# Sheet3.net
KiCad netlist of a schematic drawn in Altium Designer
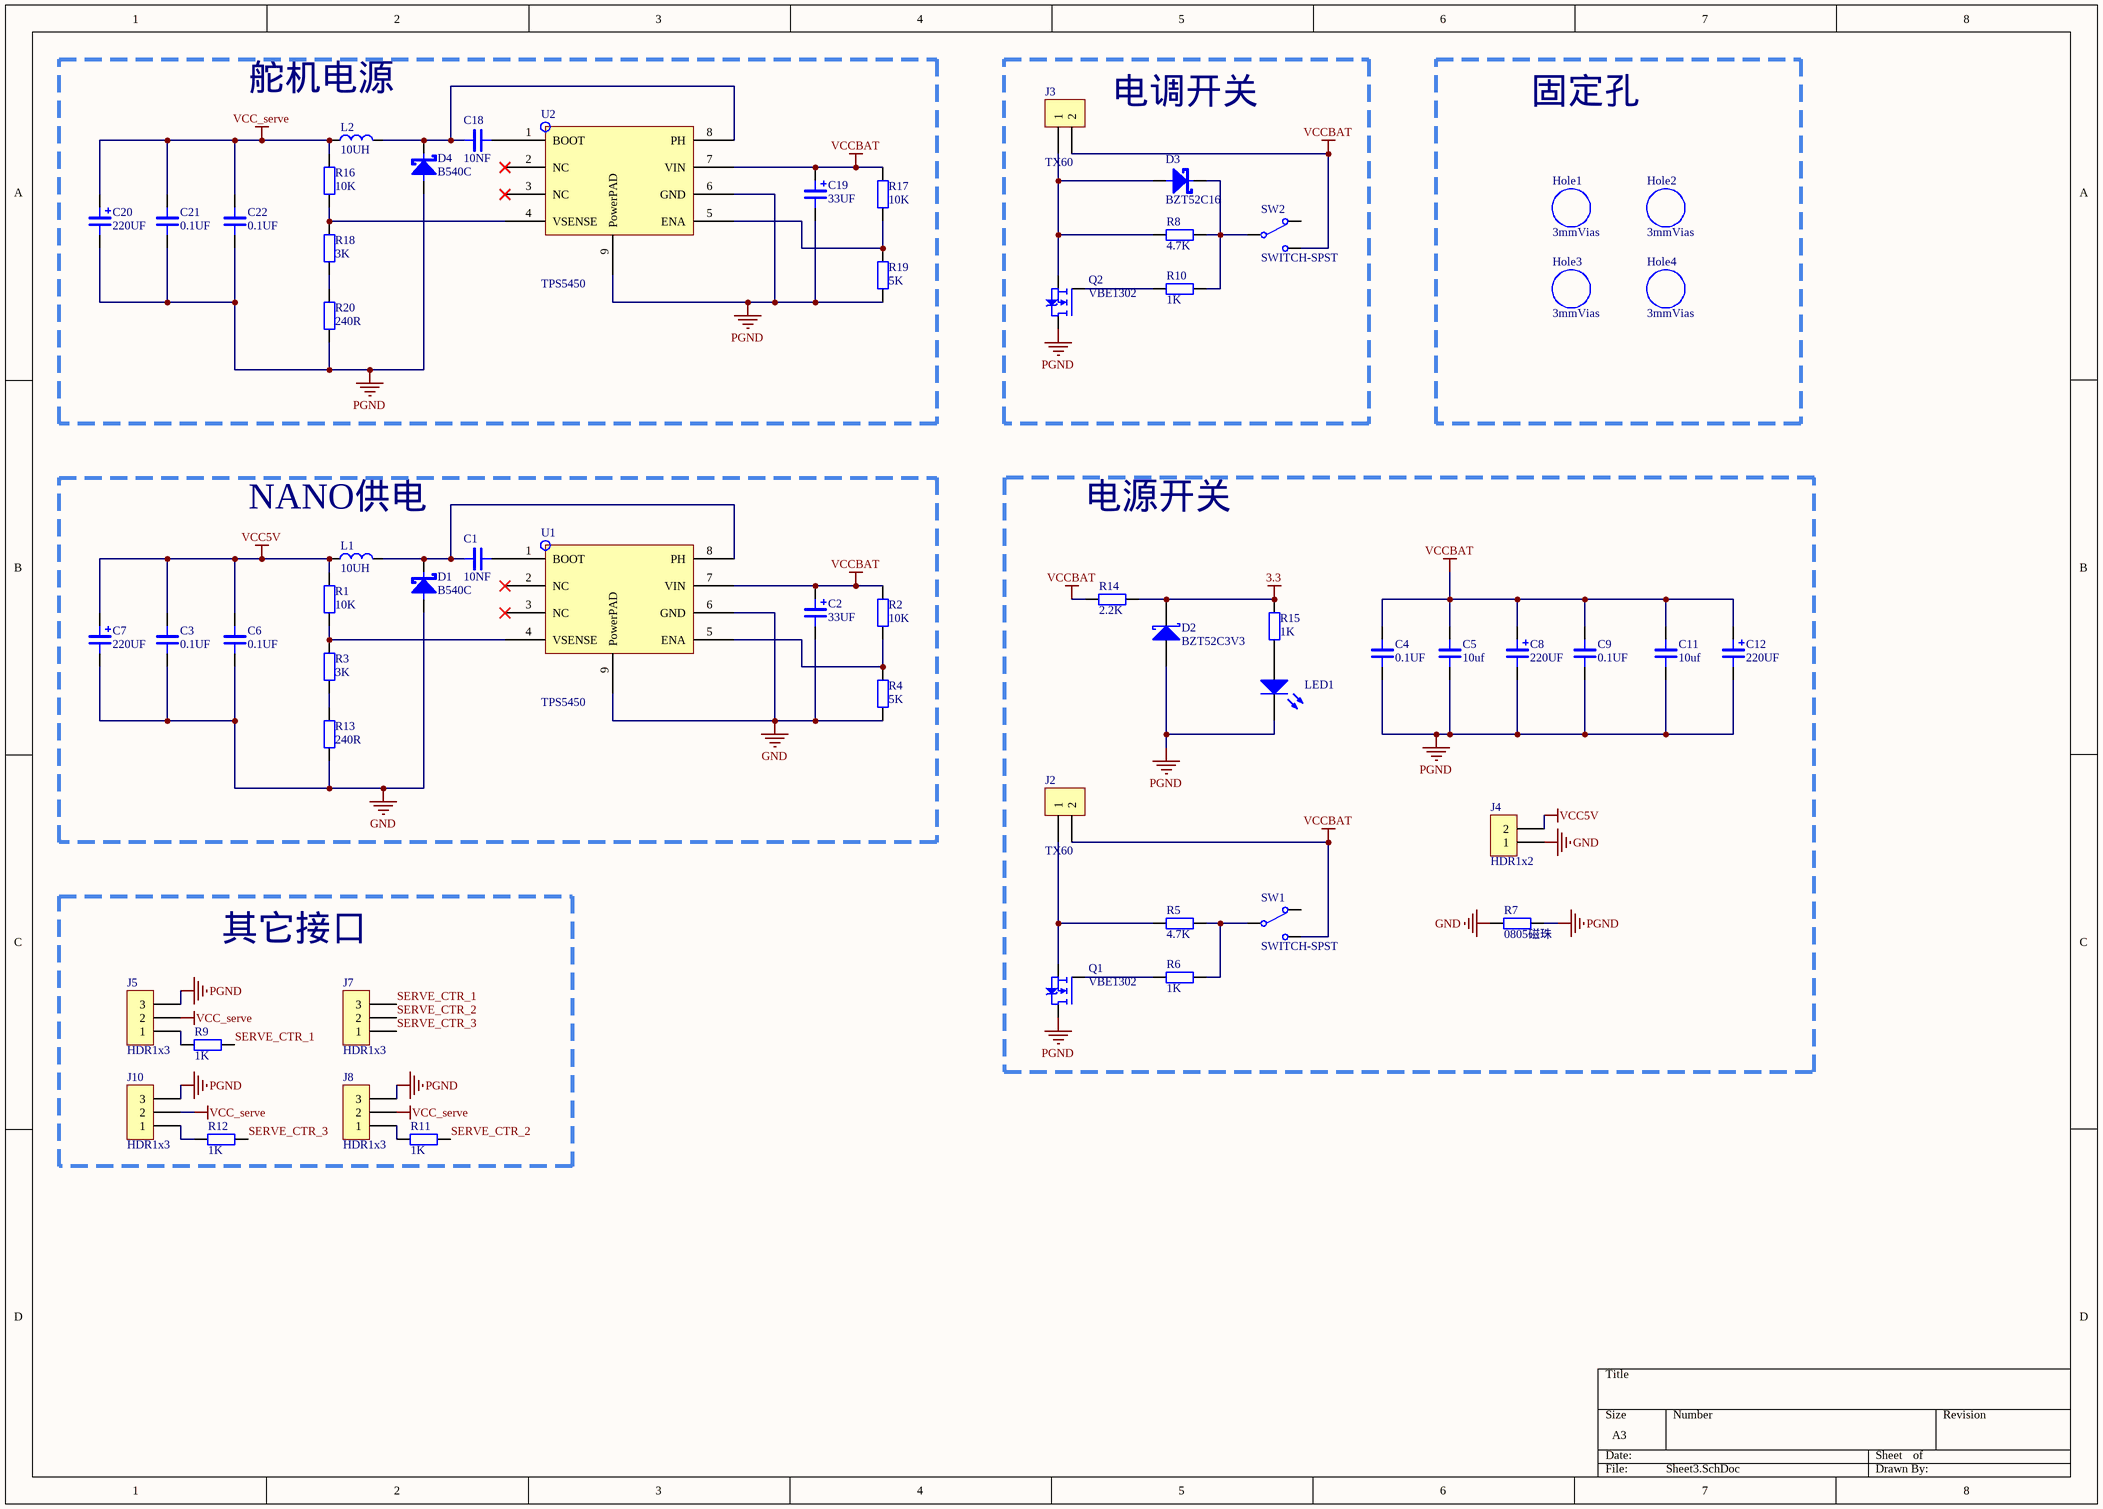
[diagram p0: Sheet3.SchDoc]

(export (version "E")
  (design (tool "Eeschema 10.0.6"))
  (components
    (comp (ref "C1")
      (value "10NF")
      (footprint "0603")
      (description "Capacitor")
      (libsource (lib "General") (part "CAP"))
    )
    (comp (ref "C2")
      (value "33UF")
      (footprint "DIP-EC2.5X5X11")
      (description "Tantalum Capacitor")
      (libsource (lib "General") (part "CAP-TANTALUM"))
    )
    (comp (ref "C3")
      (value "0.1UF")
      (footprint "0603")
      (description "Capacitor")
      (libsource (lib "General") (part "CAP"))
    )
    (comp (ref "C4")
      (value "0.1UF")
      (footprint "0603")
      (description "Capacitor")
      (libsource (lib "General") (part "CAP"))
    )
    (comp (ref "C5")
      (value "10uf")
      (footprint "0603")
      (description "Capacitor")
      (libsource (lib "General") (part "CAP"))
    )
    (comp (ref "C6")
      (value "0.1UF")
      (footprint "0603")
      (description "Capacitor")
      (libsource (lib "General") (part "CAP"))
    )
    (comp (ref "C7")
      (value "220UF")
      (footprint "DIP-EC3.5X8X11.5")
      (description "Tantalum Capacitor")
      (libsource (lib "General") (part "CAP-TANTALUM"))
    )
    (comp (ref "C8")
      (value "220UF")
      (footprint "DIP-EC3.5X8X11.5")
      (description "Tantalum Capacitor")
      (libsource (lib "General") (part "CAP-TANTALUM"))
    )
    (comp (ref "C9")
      (value "0.1UF")
      (footprint "0603")
      (description "Capacitor")
      (libsource (lib "General") (part "CAP"))
    )
    (comp (ref "C11")
      (value "10uf")
      (footprint "0603")
      (description "Capacitor")
      (libsource (lib "General") (part "CAP"))
    )
    (comp (ref "C12")
      (value "220UF")
      (footprint "DIP-EC3.5X8X11.5")
      (description "Tantalum Capacitor")
      (libsource (lib "General") (part "CAP-TANTALUM"))
    )
    (comp (ref "C18")
      (value "10NF")
      (footprint "0603")
      (description "Capacitor")
      (libsource (lib "General") (part "CAP"))
    )
    (comp (ref "C19")
      (value "33UF")
      (footprint "DIP-EC2.5X5X11")
      (description "Tantalum Capacitor")
      (libsource (lib "General") (part "CAP-TANTALUM"))
    )
    (comp (ref "C20")
      (value "220UF")
      (footprint "DIP-EC3.5X8X11.5")
      (description "Tantalum Capacitor")
      (libsource (lib "General") (part "CAP-TANTALUM"))
    )
    (comp (ref "C21")
      (value "0.1UF")
      (footprint "0603")
      (description "Capacitor")
      (libsource (lib "General") (part "CAP"))
    )
    (comp (ref "C22")
      (value "0.1UF")
      (footprint "0603")
      (description "Capacitor")
      (libsource (lib "General") (part "CAP"))
    )
    (comp (ref "D1")
      (value "B540C")
      (footprint "B540C")
      (description "Schottky Diode")
      (libsource (lib "General") (part "SS5x"))
    )
    (comp (ref "D2")
      (value "BZT52C3V3")
      (footprint "sod123")
      (description "Schottky Rectifier")
      (fields (field (name "PUBLISHER") "Altium Limited"))
      (libsource (lib "Miscellaneous Devices") (part "Diode 18TQ045"))
    )
    (comp (ref "D3")
      (value "BZT52C16")
      (footprint "sod123")
      (description "Schottky Diode")
      (libsource (lib "General") (part "SS5x"))
    )
    (comp (ref "D4")
      (value "B540C")
      (footprint "B540C")
      (description "Schottky Diode")
      (libsource (lib "General") (part "SS5x"))
    )
    (comp (ref "Hole1") (value "3mmVias") (footprint "3mm") (libsource (lib "General") (part "3mmVias")))
    (comp (ref "Hole2") (value "3mmVias") (footprint "3mm") (libsource (lib "General") (part "3mmVias")))
    (comp (ref "Hole3") (value "3mmVias") (footprint "3mm") (libsource (lib "General") (part "3mmVias")))
    (comp (ref "Hole4") (value "3mmVias") (footprint "3mm") (libsource (lib "General") (part "3mmVias")))
    (comp (ref "J2")
      (value "TX60")
      (footprint "焊盘")
      (description "Connector")
      (libsource (lib "General") (part "HDR1x2"))
    )
    (comp (ref "J3")
      (value "TX60")
      (footprint "焊盘")
      (description "Connector")
      (libsource (lib "General") (part "HDR1x2"))
    )
    (comp (ref "J4")
      (value "HDR1x2")
      (footprint "KF301")
      (description "Connector")
      (libsource (lib "") (part "HDR1x2_1"))
    )
    (comp (ref "J5")
      (value "HDR1x3")
      (footprint "PIN-3-2.54-1.0")
      (description "Connector")
      (libsource (lib "General") (part "HDR1x3"))
    )
    (comp (ref "J7")
      (value "HDR1x3")
      (footprint "PIN-3-2.54-1.0")
      (description "Connector")
      (libsource (lib "General") (part "HDR1x3"))
    )
    (comp (ref "J8")
      (value "HDR1x3")
      (footprint "PIN-3-2.54-1.0")
      (description "Connector")
      (libsource (lib "General") (part "HDR1x3"))
    )
    (comp (ref "J10")
      (value "HDR1x3")
      (footprint "PIN-3-2.54-1.0")
      (description "Connector")
      (libsource (lib "General") (part "HDR1x3"))
    )
    (comp (ref "L1")
      (value "10UH")
      (footprint "CDRH74")
      (description "Inductance")
      (libsource (lib "General") (part "INDUCTANCE"))
    )
    (comp (ref "L2")
      (value "10UH")
      (footprint "CDRH74")
      (description "Inductance")
      (libsource (lib "General") (part "INDUCTANCE"))
    )
    (comp (ref "LED1")
      (value "LED0")
      (footprint "0603-led")
      (description "Typical INFRARED GaAs LED")
      (fields (field (name "PUBLISHER") "Altium Limited"))
      (libsource (lib "Miscellaneous Devices") (part "LED0"))
    )
    (comp (ref "Q1")
      (value "VBE1302")
      (footprint "TO-252-2")
      (description "N-Channel MOSFET")
      (libsource (lib "General") (part "FDB52N20"))
    )
    (comp (ref "Q2")
      (value "VBE1302")
      (footprint "TO-252-2")
      (description "N-Channel MOSFET")
      (libsource (lib "General") (part "FDB52N20"))
    )
    (comp (ref "R1")
      (value "10K")
      (footprint "0603")
      (description "Resistor")
      (libsource (lib "General") (part "RES"))
    )
    (comp (ref "R2")
      (value "10K")
      (footprint "0603")
      (description "Resistor")
      (libsource (lib "General") (part "RES"))
    )
    (comp (ref "R3")
      (value "3K")
      (footprint "0603")
      (description "Resistor")
      (libsource (lib "General") (part "RES"))
    )
    (comp (ref "R4")
      (value "5K")
      (footprint "0603")
      (description "Resistor")
      (libsource (lib "General") (part "RES"))
    )
    (comp (ref "R5")
      (value "4.7K")
      (footprint "0603")
      (description "Resistor")
      (libsource (lib "") (part "RES_1"))
    )
    (comp (ref "R6")
      (value "1K")
      (footprint "0603")
      (description "Resistor")
      (libsource (lib "") (part "RES_1"))
    )
    (comp (ref "R7")
      (value "0805磁珠")
      (footprint "0805")
      (description "Resistor")
      (libsource (lib "") (part "RES_2"))
    )
    (comp (ref "R8")
      (value "4.7K")
      (footprint "0603")
      (description "Resistor")
      (libsource (lib "") (part "RES_1"))
    )
    (comp (ref "R9")
      (value "1K")
      (footprint "0603")
      (description "Resistor")
      (libsource (lib "") (part "RES_1"))
    )
    (comp (ref "R10")
      (value "1K")
      (footprint "0603")
      (description "Resistor")
      (libsource (lib "") (part "RES_1"))
    )
    (comp (ref "R11")
      (value "1K")
      (footprint "0603")
      (description "Resistor")
      (libsource (lib "") (part "RES_1"))
    )
    (comp (ref "R12")
      (value "1K")
      (footprint "0603")
      (description "Resistor")
      (libsource (lib "") (part "RES_1"))
    )
    (comp (ref "R13")
      (value "240R")
      (footprint "0603")
      (description "Resistor")
      (libsource (lib "General") (part "RES"))
    )
    (comp (ref "R14")
      (value "2.2K")
      (footprint "0603")
      (description "Resistor")
      (libsource (lib "") (part "RES_2"))
    )
    (comp (ref "R15")
      (value "1K")
      (footprint "0603")
      (description "Resistor")
      (libsource (lib "") (part "RES_3"))
    )
    (comp (ref "R16")
      (value "10K")
      (footprint "0603")
      (description "Resistor")
      (libsource (lib "General") (part "RES"))
    )
    (comp (ref "R17")
      (value "10K")
      (footprint "0603")
      (description "Resistor")
      (libsource (lib "General") (part "RES"))
    )
    (comp (ref "R18")
      (value "3K")
      (footprint "0603")
      (description "Resistor")
      (libsource (lib "General") (part "RES"))
    )
    (comp (ref "R19")
      (value "5K")
      (footprint "0603")
      (description "Resistor")
      (libsource (lib "General") (part "RES"))
    )
    (comp (ref "R20")
      (value "240R")
      (footprint "0603")
      (description "Resistor")
      (libsource (lib "General") (part "RES"))
    )
    (comp (ref "SW1")
      (value "SWITCH-SPST")
      (footprint "ss12d10")
      (description "Switch")
      (libsource (lib "General") (part "SWITCH-SPST"))
    )
    (comp (ref "SW2")
      (value "SWITCH-SPST")
      (footprint "ss12d10")
      (description "Switch")
      (libsource (lib "General") (part "SWITCH-SPST"))
    )
    (comp (ref "U1") (value "TPS5450") (footprint "TPS5450") (libsource (lib "General") (part "TPS5450")))
    (comp (ref "U2") (value "TPS5450") (footprint "TPS5450") (libsource (lib "General") (part "TPS5450")))
  )
  (nets
    (net (code "1") (name "/SERVE_CTR_1") (class "Default")
      (node (ref "J7") (pin "3") (pinfunction "3_3") (pintype "passive"))
      (node (ref "R9") (pin "2") (pinfunction "2_2") (pintype "passive"))
    )
    (net (code "2") (name "/SERVE_CTR_2") (class "Default")
      (node (ref "J7") (pin "2") (pinfunction "2_2") (pintype "passive"))
      (node (ref "R11") (pin "2") (pinfunction "2_2") (pintype "passive"))
    )
    (net (code "3") (name "/SERVE_CTR_3") (class "Default")
      (node (ref "J7") (pin "1") (pinfunction "1_1") (pintype "passive"))
      (node (ref "R12") (pin "2") (pinfunction "2_2") (pintype "passive"))
    )
    (net (code "4") (name "3.3") (class "Default")
      (node (ref "D2") (pin "1") (pinfunction "K_1") (pintype "passive"))
      (node (ref "R14") (pin "1") (pinfunction "1_1") (pintype "passive"))
      (node (ref "R15") (pin "1") (pinfunction "1_1") (pintype "passive"))
    )
    (net (code "5") (name "GND") (class "Default")
      (node (ref "C2") (pin "2") (pinfunction "2_2") (pintype "passive"))
      (node (ref "C3") (pin "1") (pinfunction "1_1") (pintype "passive"))
      (node (ref "C6") (pin "1") (pinfunction "1_1") (pintype "passive"))
      (node (ref "C7") (pin "2") (pinfunction "2_2") (pintype "passive"))
      (node (ref "D1") (pin "1") (pinfunction "A_1") (pintype "passive"))
      (node (ref "J4") (pin "1") (pinfunction "1_1") (pintype "passive"))
      (node (ref "R13") (pin "1") (pinfunction "1_1") (pintype "passive"))
      (node (ref "R4") (pin "1") (pinfunction "1_1") (pintype "passive"))
      (node (ref "R7") (pin "2") (pinfunction "2_2") (pintype "passive"))
      (node (ref "U1") (pin "6") (pinfunction "GND_6") (pintype "passive"))
      (node (ref "U1") (pin "9") (pinfunction "PowerPAD_9") (pintype "passive"))
    )
    (net (code "6") (name "Net-(D1-C)") (class "Default")
      (node (ref "C1") (pin "2") (pinfunction "2_2") (pintype "passive"))
      (node (ref "D1") (pin "2") (pinfunction "C_2") (pintype "passive"))
      (node (ref "L1") (pin "2") (pinfunction "2_2") (pintype "passive"))
      (node (ref "U1") (pin "8") (pinfunction "PH_8") (pintype "passive"))
    )
    (net (code "7") (name "Net-(D3-A)") (class "Default")
      (node (ref "D3") (pin "1") (pinfunction "A_1") (pintype "passive"))
      (node (ref "J3") (pin "1") (pinfunction "1_1") (pintype "passive"))
      (node (ref "Q2") (pin "3") (pinfunction "S_3") (pintype "passive"))
      (node (ref "R8") (pin "1") (pinfunction "1_1") (pintype "passive"))
    )
    (net (code "8") (name "Net-(D3-C)") (class "Default")
      (node (ref "D3") (pin "2") (pinfunction "C_2") (pintype "passive"))
      (node (ref "R10") (pin "2") (pinfunction "2_2") (pintype "passive"))
      (node (ref "R8") (pin "2") (pinfunction "2_2") (pintype "passive"))
      (node (ref "SW2") (pin "2") (pinfunction "2_2") (pintype "passive"))
    )
    (net (code "9") (name "Net-(D4-C)") (class "Default")
      (node (ref "C18") (pin "2") (pinfunction "2_2") (pintype "passive"))
      (node (ref "D4") (pin "2") (pinfunction "C_2") (pintype "passive"))
      (node (ref "L2") (pin "2") (pinfunction "2_2") (pintype "passive"))
      (node (ref "U2") (pin "8") (pinfunction "PH_8") (pintype "passive"))
    )
    (net (code "10") (name "Net-(J5-Pad1)") (class "Default")
      (node (ref "J5") (pin "1") (pinfunction "1_1") (pintype "passive"))
      (node (ref "R9") (pin "1") (pinfunction "1_1") (pintype "passive"))
    )
    (net (code "11") (name "Net-(J8-Pad1)") (class "Default")
      (node (ref "J8") (pin "1") (pinfunction "1_1") (pintype "passive"))
      (node (ref "R11") (pin "1") (pinfunction "1_1") (pintype "passive"))
    )
    (net (code "12") (name "Net-(J10-Pad1)") (class "Default")
      (node (ref "J10") (pin "1") (pinfunction "1_1") (pintype "passive"))
      (node (ref "R12") (pin "1") (pinfunction "1_1") (pintype "passive"))
    )
    (net (code "13") (name "Net-(LED1-A)") (class "Default")
      (node (ref "LED1") (pin "1") (pinfunction "A_1") (pintype "passive"))
      (node (ref "R15") (pin "2") (pinfunction "2_2") (pintype "passive"))
    )
    (net (code "14") (name "Net-(Q1-G)") (class "Default")
      (node (ref "Q1") (pin "1") (pinfunction "G_1") (pintype "passive"))
      (node (ref "R6") (pin "1") (pinfunction "1_1") (pintype "passive"))
    )
    (net (code "15") (name "Net-(Q1-S)") (class "Default")
      (node (ref "J2") (pin "1") (pinfunction "1_1") (pintype "passive"))
      (node (ref "Q1") (pin "3") (pinfunction "S_3") (pintype "passive"))
      (node (ref "R5") (pin "1") (pinfunction "1_1") (pintype "passive"))
    )
    (net (code "16") (name "Net-(Q2-G)") (class "Default")
      (node (ref "Q2") (pin "1") (pinfunction "G_1") (pintype "passive"))
      (node (ref "R10") (pin "1") (pinfunction "1_1") (pintype "passive"))
    )
    (net (code "17") (name "Net-(R5-Pad2)") (class "Default")
      (node (ref "R5") (pin "2") (pinfunction "2_2") (pintype "passive"))
      (node (ref "R6") (pin "2") (pinfunction "2_2") (pintype "passive"))
      (node (ref "SW1") (pin "2") (pinfunction "2_2") (pintype "passive"))
    )
    (net (code "18") (name "Net-(R13-Pad2)") (class "Default")
      (node (ref "R13") (pin "2") (pinfunction "2_2") (pintype "passive"))
      (node (ref "R3") (pin "1") (pinfunction "1_1") (pintype "passive"))
    )
    (net (code "19") (name "Net-(R18-Pad1)") (class "Default")
      (node (ref "R18") (pin "1") (pinfunction "1_1") (pintype "passive"))
      (node (ref "R20") (pin "2") (pinfunction "2_2") (pintype "passive"))
    )
    (net (code "20") (name "Net-(U1-BOOT)") (class "Default")
      (node (ref "C1") (pin "1") (pinfunction "1_1") (pintype "passive"))
      (node (ref "U1") (pin "1") (pinfunction "BOOT_1") (pintype "passive"))
    )
    (net (code "21") (name "Net-(U1-ENA)") (class "Default")
      (node (ref "R2") (pin "1") (pinfunction "1_1") (pintype "passive"))
      (node (ref "R4") (pin "2") (pinfunction "2_2") (pintype "passive"))
      (node (ref "U1") (pin "5") (pinfunction "ENA_5") (pintype "passive"))
    )
    (net (code "22") (name "Net-(U1-VSENSE)") (class "Default")
      (node (ref "R1") (pin "1") (pinfunction "1_1") (pintype "passive"))
      (node (ref "R3") (pin "2") (pinfunction "2_2") (pintype "passive"))
      (node (ref "U1") (pin "4") (pinfunction "VSENSE_4") (pintype "passive"))
    )
    (net (code "23") (name "Net-(U2-BOOT)") (class "Default")
      (node (ref "C18") (pin "1") (pinfunction "1_1") (pintype "passive"))
      (node (ref "U2") (pin "1") (pinfunction "BOOT_1") (pintype "passive"))
    )
    (net (code "24") (name "Net-(U2-ENA)") (class "Default")
      (node (ref "R17") (pin "1") (pinfunction "1_1") (pintype "passive"))
      (node (ref "R19") (pin "2") (pinfunction "2_2") (pintype "passive"))
      (node (ref "U2") (pin "5") (pinfunction "ENA_5") (pintype "passive"))
    )
    (net (code "25") (name "Net-(U2-VSENSE)") (class "Default")
      (node (ref "R16") (pin "1") (pinfunction "1_1") (pintype "passive"))
      (node (ref "R18") (pin "2") (pinfunction "2_2") (pintype "passive"))
      (node (ref "U2") (pin "4") (pinfunction "VSENSE_4") (pintype "passive"))
    )
    (net (code "26") (name "PGND") (class "Default")
      (node (ref "C11") (pin "1") (pinfunction "1_1") (pintype "passive"))
      (node (ref "C12") (pin "2") (pinfunction "2_2") (pintype "passive"))
      (node (ref "C19") (pin "2") (pinfunction "2_2") (pintype "passive"))
      (node (ref "C20") (pin "2") (pinfunction "2_2") (pintype "passive"))
      (node (ref "C21") (pin "1") (pinfunction "1_1") (pintype "passive"))
      (node (ref "C22") (pin "1") (pinfunction "1_1") (pintype "passive"))
      (node (ref "C4") (pin "1") (pinfunction "1_1") (pintype "passive"))
      (node (ref "C5") (pin "1") (pinfunction "1_1") (pintype "passive"))
      (node (ref "C8") (pin "2") (pinfunction "2_2") (pintype "passive"))
      (node (ref "C9") (pin "1") (pinfunction "1_1") (pintype "passive"))
      (node (ref "D2") (pin "3") (pinfunction "A_3") (pintype "passive"))
      (node (ref "D4") (pin "1") (pinfunction "A_1") (pintype "passive"))
      (node (ref "J10") (pin "3") (pinfunction "3_3") (pintype "passive"))
      (node (ref "J5") (pin "3") (pinfunction "3_3") (pintype "passive"))
      (node (ref "J8") (pin "3") (pinfunction "3_3") (pintype "passive"))
      (node (ref "LED1") (pin "2") (pinfunction "K_2") (pintype "passive"))
      (node (ref "Q1") (pin "4") (pinfunction "D_4") (pintype "passive"))
      (node (ref "Q2") (pin "4") (pinfunction "D_4") (pintype "passive"))
      (node (ref "R19") (pin "1") (pinfunction "1_1") (pintype "passive"))
      (node (ref "R20") (pin "1") (pinfunction "1_1") (pintype "passive"))
      (node (ref "R7") (pin "1") (pinfunction "1_1") (pintype "passive"))
      (node (ref "U2") (pin "6") (pinfunction "GND_6") (pintype "passive"))
      (node (ref "U2") (pin "9") (pinfunction "PowerPAD_9") (pintype "passive"))
    )
    (net (code "27") (name "VCC5V") (class "Default")
      (node (ref "C3") (pin "2") (pinfunction "2_2") (pintype "passive"))
      (node (ref "C6") (pin "2") (pinfunction "2_2") (pintype "passive"))
      (node (ref "C7") (pin "1") (pinfunction "1_1") (pintype "passive"))
      (node (ref "J4") (pin "2") (pinfunction "2_2") (pintype "passive"))
      (node (ref "L1") (pin "1") (pinfunction "1_1") (pintype "passive"))
      (node (ref "R1") (pin "2") (pinfunction "2_2") (pintype "passive"))
    )
    (net (code "28") (name "VCCBAT") (class "Default")
      (node (ref "C11") (pin "2") (pinfunction "2_2") (pintype "passive"))
      (node (ref "C12") (pin "1") (pinfunction "1_1") (pintype "passive"))
      (node (ref "C19") (pin "1") (pinfunction "1_1") (pintype "passive"))
      (node (ref "C2") (pin "1") (pinfunction "1_1") (pintype "passive"))
      (node (ref "C4") (pin "2") (pinfunction "2_2") (pintype "passive"))
      (node (ref "C5") (pin "2") (pinfunction "2_2") (pintype "passive"))
      (node (ref "C8") (pin "1") (pinfunction "1_1") (pintype "passive"))
      (node (ref "C9") (pin "2") (pinfunction "2_2") (pintype "passive"))
      (node (ref "J2") (pin "2") (pinfunction "2_2") (pintype "passive"))
      (node (ref "J3") (pin "2") (pinfunction "2_2") (pintype "passive"))
      (node (ref "R14") (pin "2") (pinfunction "2_2") (pintype "passive"))
      (node (ref "R17") (pin "2") (pinfunction "2_2") (pintype "passive"))
      (node (ref "R2") (pin "2") (pinfunction "2_2") (pintype "passive"))
      (node (ref "SW1") (pin "3") (pinfunction "3_3") (pintype "passive"))
      (node (ref "SW2") (pin "3") (pinfunction "3_3") (pintype "passive"))
      (node (ref "U1") (pin "7") (pinfunction "VIN_7") (pintype "passive"))
      (node (ref "U2") (pin "7") (pinfunction "VIN_7") (pintype "passive"))
    )
    (net (code "29") (name "VCC_serve") (class "Default")
      (node (ref "C20") (pin "1") (pinfunction "1_1") (pintype "passive"))
      (node (ref "C21") (pin "2") (pinfunction "2_2") (pintype "passive"))
      (node (ref "C22") (pin "2") (pinfunction "2_2") (pintype "passive"))
      (node (ref "J10") (pin "2") (pinfunction "2_2") (pintype "passive"))
      (node (ref "J5") (pin "2") (pinfunction "2_2") (pintype "passive"))
      (node (ref "J8") (pin "2") (pinfunction "2_2") (pintype "passive"))
      (node (ref "L2") (pin "1") (pinfunction "1_1") (pintype "passive"))
      (node (ref "R16") (pin "2") (pinfunction "2_2") (pintype "passive"))
    )
    (net (code "30") (name "unconnected-(SW1-Pad1)") (class "Default")
      (node (ref "SW1") (pin "1") (pinfunction "1_1") (pintype "passive"))
    )
    (net (code "31") (name "unconnected-(SW2-Pad1)") (class "Default")
      (node (ref "SW2") (pin "1") (pinfunction "1_1") (pintype "passive"))
    )
    (net (code "32") (name "unconnected-(U1-NC-Pad2)") (class "Default")
      (node (ref "U1") (pin "2") (pinfunction "NC_2") (pintype "passive+no_connect"))
    )
    (net (code "33") (name "unconnected-(U1-NC-Pad3)") (class "Default")
      (node (ref "U1") (pin "3") (pinfunction "NC_3") (pintype "passive+no_connect"))
    )
    (net (code "34") (name "unconnected-(U2-NC-Pad2)") (class "Default")
      (node (ref "U2") (pin "2") (pinfunction "NC_2") (pintype "passive+no_connect"))
    )
    (net (code "35") (name "unconnected-(U2-NC-Pad3)") (class "Default")
      (node (ref "U2") (pin "3") (pinfunction "NC_3") (pintype "passive+no_connect"))
    )
  )
)
